# smartwatch-bottom.net
KiCad netlist of a schematic drawn in EAGLE
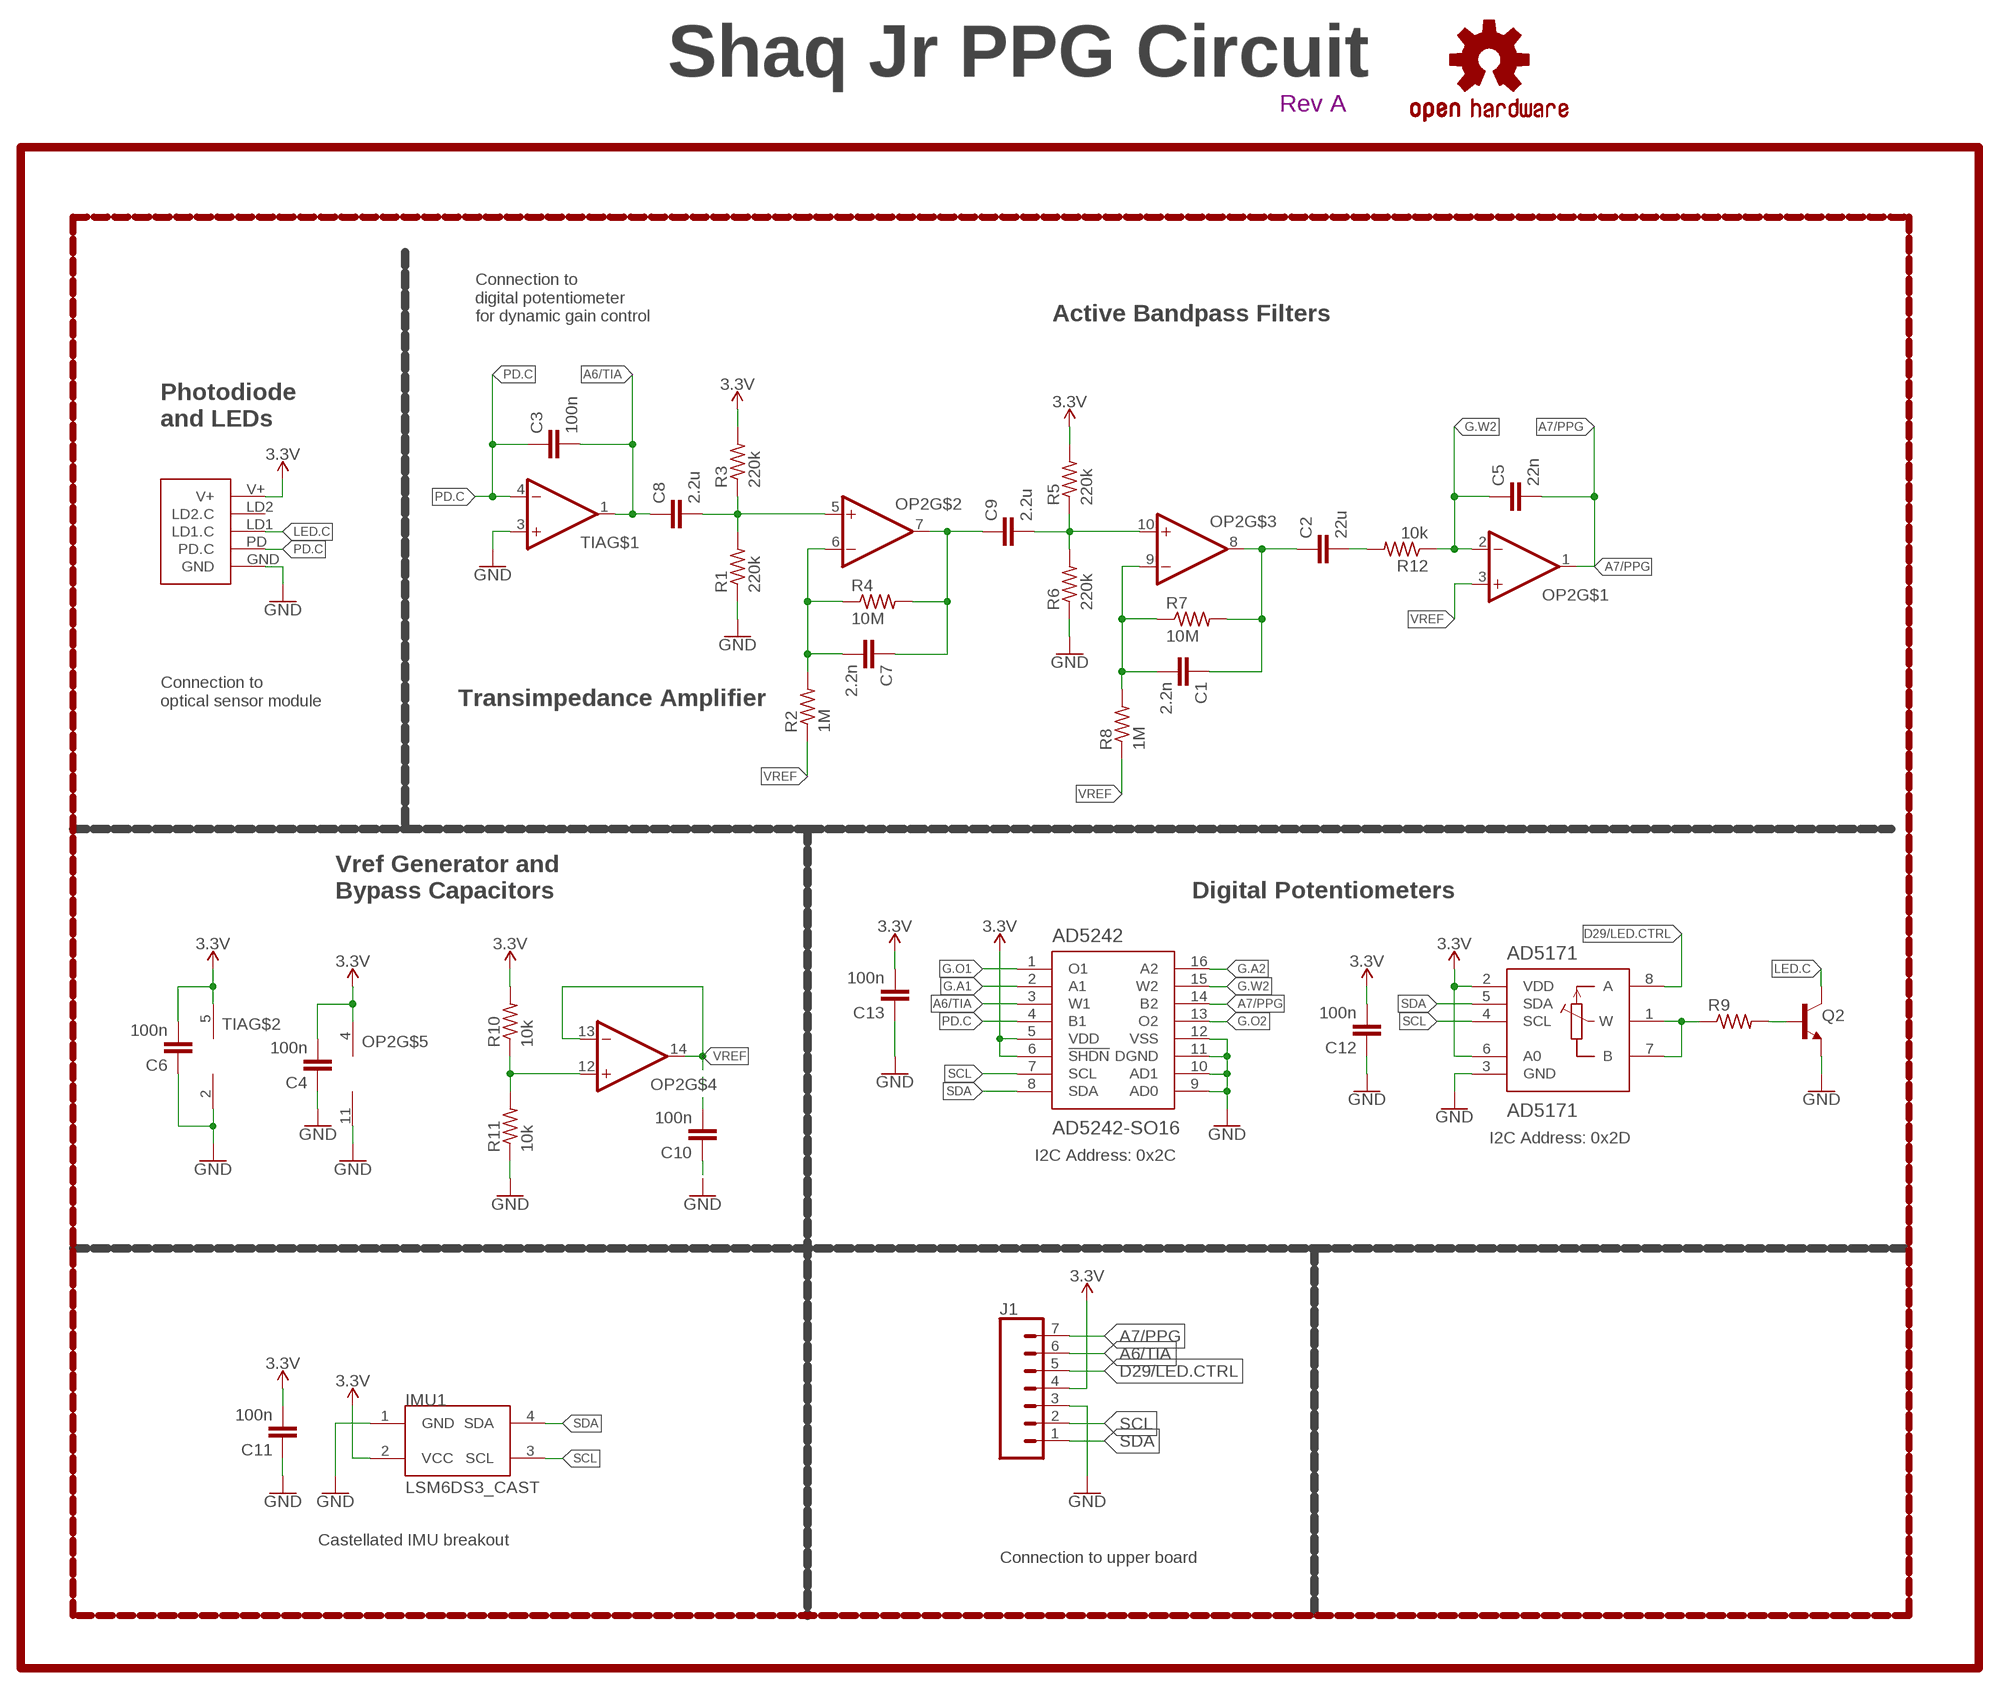
[diagram p0: schematic, sheet 1]

(export (version "E")
  (design (tool "Eeschema 10.0.6"))
  (components
    (comp (ref "AD5171")
      (value "AD5171")
      (footprint "eagle-import:SOT-23-8")
      (libsource (lib "eagle-import") (part "AD5171"))
    )
    (comp (ref "AD5242")
      (value "AD5242-SO16")
      (footprint "eagle-import:SO16")
      (libsource (lib "eagle-import") (part "AD5242-SO16"))
    )
    (comp (ref "C1")
      (value "2.2n")
      (footprint "eagle-import:C0603")
      (libsource (lib "eagle-import") (part "CAPACITOR0603"))
    )
    (comp (ref "C2")
      (value "22u")
      (footprint "eagle-import:C0603")
      (libsource (lib "eagle-import") (part "CAPACITOR0603"))
    )
    (comp (ref "C3")
      (value "100n")
      (footprint "eagle-import:C0603")
      (libsource (lib "eagle-import") (part "CAPACITOR0603"))
    )
    (comp (ref "C4")
      (value "100n")
      (footprint "eagle-import:C0603")
      (libsource (lib "eagle-import") (part "CAPACITOR0603"))
    )
    (comp (ref "C5")
      (value "22n")
      (footprint "eagle-import:C0603")
      (libsource (lib "eagle-import") (part "CAPACITOR0603"))
    )
    (comp (ref "C6")
      (value "100n")
      (footprint "eagle-import:C0603")
      (libsource (lib "eagle-import") (part "CAPACITOR0603"))
    )
    (comp (ref "C7")
      (value "2.2n")
      (footprint "eagle-import:C0603")
      (libsource (lib "eagle-import") (part "CAPACITOR0603"))
    )
    (comp (ref "C8")
      (value "2.2u")
      (footprint "eagle-import:C0603")
      (libsource (lib "eagle-import") (part "CAPACITOR0603"))
    )
    (comp (ref "C9")
      (value "2.2u")
      (footprint "eagle-import:C0603")
      (libsource (lib "eagle-import") (part "CAPACITOR0603"))
    )
    (comp (ref "C10")
      (value "100n")
      (footprint "eagle-import:C0603")
      (libsource (lib "eagle-import") (part "CAPACITOR0603"))
    )
    (comp (ref "C11")
      (value "100n")
      (footprint "eagle-import:C0603")
      (libsource (lib "eagle-import") (part "CAPACITOR0603"))
    )
    (comp (ref "C12")
      (value "100n")
      (footprint "eagle-import:C0603")
      (libsource (lib "eagle-import") (part "CAPACITOR0603"))
    )
    (comp (ref "C13")
      (value "100n")
      (footprint "eagle-import:C0603")
      (libsource (lib "eagle-import") (part "CAPACITOR0603"))
    )
    (comp (ref "IMU1")
      (value "LSM6DS3_CAST")
      (footprint "eagle-import:LSM6DS3_CAST")
      (libsource (lib "eagle-import") (part "LSM6DS3_CAST"))
    )
    (comp (ref "J1")
      (value "CONN_07-1.27MM")
      (footprint "eagle-import:1X07_1.27MM")
      (libsource (lib "eagle-import") (part "CONN_07-1.27MM"))
    )
    (comp (ref "LOGO1")
      (value "REVISION.A")
      (footprint "eagle-import:REV.A")
      (libsource (lib "eagle-import") (part "REVISION.A"))
    )
    (comp (ref "LOGO2")
      (value "OSHW-LOGOS")
      (footprint "eagle-import:OSHW-LOGO-S")
      (libsource (lib "eagle-import") (part "OSHW-LOGOS"))
    )
    (comp (ref "OP2")
      (value "OP-QUAD-SO14")
      (footprint "eagle-import:SO14")
      (libsource (lib "eagle-import") (part "OP-QUAD-SO14"))
    )
    (comp (ref "Q2")
      (value "NPN-GENERIC")
      (footprint "eagle-import:SOT23-3")
      (libsource (lib "eagle-import") (part "NPN-GENERIC"))
    )
    (comp (ref "R1")
      (value "220k")
      (footprint "eagle-import:R0603")
      (libsource (lib "eagle-import") (part "RESISTOR0603"))
    )
    (comp (ref "R2")
      (value "1M")
      (footprint "eagle-import:R0603")
      (libsource (lib "eagle-import") (part "RESISTOR0603"))
    )
    (comp (ref "R3")
      (value "220k")
      (footprint "eagle-import:R0603")
      (libsource (lib "eagle-import") (part "RESISTOR0603"))
    )
    (comp (ref "R4")
      (value "10M")
      (footprint "eagle-import:R0603")
      (libsource (lib "eagle-import") (part "RESISTOR0603"))
    )
    (comp (ref "R5")
      (value "220k")
      (footprint "eagle-import:R0603")
      (libsource (lib "eagle-import") (part "RESISTOR0603"))
    )
    (comp (ref "R6")
      (value "220k")
      (footprint "eagle-import:R0603")
      (libsource (lib "eagle-import") (part "RESISTOR0603"))
    )
    (comp (ref "R7")
      (value "10M")
      (footprint "eagle-import:R0603")
      (libsource (lib "eagle-import") (part "RESISTOR0603"))
    )
    (comp (ref "R8")
      (value "1M")
      (footprint "eagle-import:R0603")
      (libsource (lib "eagle-import") (part "RESISTOR0603"))
    )
    (comp (ref "R9")
      (value "RESISTOR0603")
      (footprint "eagle-import:R0603")
      (libsource (lib "eagle-import") (part "RESISTOR0603"))
    )
    (comp (ref "R10")
      (value "10k")
      (footprint "eagle-import:R0402")
      (libsource (lib "eagle-import") (part "RESISTOR0402"))
    )
    (comp (ref "R11")
      (value "10k")
      (footprint "eagle-import:R0402")
      (libsource (lib "eagle-import") (part "RESISTOR0402"))
    )
    (comp (ref "R12")
      (value "10k")
      (footprint "eagle-import:R0603")
      (libsource (lib "eagle-import") (part "RESISTOR0603"))
    )
    (comp (ref "TIA")
      (value "OP-SINGLEOT")
      (footprint "eagle-import:SOT23-5")
      (libsource (lib "eagle-import") (part "OP-SINGLEOT"))
    )
    (comp (ref "U$1")
      (value "PPG.MODULE.2")
      (footprint "eagle-import:PPG.MODULE.2")
      (libsource (lib "eagle-import") (part "PPG.MODULE.2"))
    )
  )
  (nets
    (net (code "1") (name "3.3V") (class "Default")
      (node (ref "AD5171") (pin "2") (pinfunction "VDD_2") (pintype "bidirectional"))
      (node (ref "AD5171") (pin "6") (pinfunction "A0_6") (pintype "bidirectional"))
      (node (ref "AD5242") (pin "5") (pinfunction "VDD_5") (pintype "bidirectional"))
      (node (ref "AD5242") (pin "6") (pinfunction "~{SHDN}_6") (pintype "bidirectional"))
      (node (ref "C11") (pin "2") (pinfunction "2_2") (pintype "passive"))
      (node (ref "C12") (pin "2") (pinfunction "2_2") (pintype "passive"))
      (node (ref "C13") (pin "2") (pinfunction "2_2") (pintype "passive"))
      (node (ref "C4") (pin "2") (pinfunction "2_2") (pintype "passive"))
      (node (ref "C6") (pin "2") (pinfunction "2_2") (pintype "passive"))
      (node (ref "IMU1") (pin "2") (pinfunction "VCC_2") (pintype "bidirectional"))
      (node (ref "J1") (pin "4") (pinfunction "4_4") (pintype "passive"))
      (node (ref "OP2") (pin "4") (pinfunction "V+_4") (pintype "power_in"))
      (node (ref "R10") (pin "2") (pinfunction "2_2") (pintype "passive"))
      (node (ref "R3") (pin "2") (pinfunction "2_2") (pintype "passive"))
      (node (ref "R5") (pin "2") (pinfunction "2_2") (pintype "passive"))
      (node (ref "TIA") (pin "5") (pinfunction "V+_5") (pintype "power_in"))
      (node (ref "U$1") (pin "V+") (pinfunction "V+_V+") (pintype "bidirectional"))
    )
    (net (code "2") (name "A6{slash}TIA") (class "Default")
      (node (ref "AD5242") (pin "3") (pinfunction "W1_3") (pintype "bidirectional"))
      (node (ref "C3") (pin "2") (pinfunction "2_2") (pintype "passive"))
      (node (ref "C8") (pin "1") (pinfunction "1_1") (pintype "passive"))
      (node (ref "J1") (pin "6") (pinfunction "6_6") (pintype "passive"))
      (node (ref "TIA") (pin "1") (pinfunction "OUT_1") (pintype "output"))
    )
    (net (code "3") (name "A7{slash}PPG") (class "Default")
      (node (ref "AD5242") (pin "14") (pinfunction "B2_14") (pintype "bidirectional"))
      (node (ref "C5") (pin "2") (pinfunction "2_2") (pintype "passive"))
      (node (ref "J1") (pin "7") (pinfunction "7_7") (pintype "passive"))
      (node (ref "OP2") (pin "1") (pinfunction "OUT_1") (pintype "output"))
    )
    (net (code "4") (name "D29{slash}LED.CTRL") (class "Default")
      (node (ref "AD5171") (pin "8") (pinfunction "A_8") (pintype "bidirectional"))
      (node (ref "J1") (pin "5") (pinfunction "5_5") (pintype "passive"))
    )
    (net (code "5") (name "G.A1") (class "Default")
      (node (ref "AD5242") (pin "2") (pinfunction "A1_2") (pintype "bidirectional"))
    )
    (net (code "6") (name "G.A2") (class "Default")
      (node (ref "AD5242") (pin "16") (pinfunction "A2_16") (pintype "bidirectional"))
    )
    (net (code "7") (name "G.O1") (class "Default")
      (node (ref "AD5242") (pin "1") (pinfunction "O1_1") (pintype "bidirectional"))
    )
    (net (code "8") (name "G.O2") (class "Default")
      (node (ref "AD5242") (pin "13") (pinfunction "O2_13") (pintype "bidirectional"))
    )
    (net (code "9") (name "G.W2") (class "Default")
      (node (ref "AD5242") (pin "15") (pinfunction "W2_15") (pintype "bidirectional"))
      (node (ref "C5") (pin "1") (pinfunction "1_1") (pintype "passive"))
      (node (ref "OP2") (pin "2") (pinfunction "-IN_2") (pintype "input"))
      (node (ref "R12") (pin "1") (pinfunction "1_1") (pintype "passive"))
    )
    (net (code "10") (name "GND") (class "Default")
      (node (ref "AD5171") (pin "3") (pinfunction "GND_3") (pintype "bidirectional"))
      (node (ref "AD5242") (pin "10") (pinfunction "AD1_10") (pintype "bidirectional"))
      (node (ref "AD5242") (pin "11") (pinfunction "DGND_11") (pintype "bidirectional"))
      (node (ref "AD5242") (pin "12") (pinfunction "VSS_12") (pintype "bidirectional"))
      (node (ref "AD5242") (pin "9") (pinfunction "AD0_9") (pintype "bidirectional"))
      (node (ref "C10") (pin "1") (pinfunction "1_1") (pintype "passive"))
      (node (ref "C11") (pin "1") (pinfunction "1_1") (pintype "passive"))
      (node (ref "C12") (pin "1") (pinfunction "1_1") (pintype "passive"))
      (node (ref "C13") (pin "1") (pinfunction "1_1") (pintype "passive"))
      (node (ref "C4") (pin "1") (pinfunction "1_1") (pintype "passive"))
      (node (ref "C6") (pin "1") (pinfunction "1_1") (pintype "passive"))
      (node (ref "IMU1") (pin "1") (pinfunction "GND_1") (pintype "bidirectional"))
      (node (ref "J1") (pin "3") (pinfunction "3_3") (pintype "passive"))
      (node (ref "OP2") (pin "11") (pinfunction "V-_11") (pintype "power_in"))
      (node (ref "Q2") (pin "2") (pinfunction "E_2") (pintype "passive"))
      (node (ref "R1") (pin "1") (pinfunction "1_1") (pintype "passive"))
      (node (ref "R11") (pin "1") (pinfunction "1_1") (pintype "passive"))
      (node (ref "R6") (pin "1") (pinfunction "1_1") (pintype "passive"))
      (node (ref "TIA") (pin "2") (pinfunction "V-_2") (pintype "power_in"))
      (node (ref "TIA") (pin "3") (pinfunction "+IN_3") (pintype "input"))
      (node (ref "U$1") (pin "GND") (pinfunction "GND_GND") (pintype "bidirectional"))
    )
    (net (code "11") (name "LED.C") (class "Default")
      (node (ref "Q2") (pin "3") (pinfunction "C_3") (pintype "passive"))
      (node (ref "U$1") (pin "LD1") (pinfunction "LD1.C_LD1") (pintype "bidirectional"))
    )
    (net (code "12") (name "Net-(AD5171-B)") (class "Default")
      (node (ref "AD5171") (pin "1") (pinfunction "W_1") (pintype "bidirectional"))
      (node (ref "AD5171") (pin "7") (pinfunction "B_7") (pintype "bidirectional"))
      (node (ref "R9") (pin "1") (pinfunction "1_1") (pintype "passive"))
    )
    (net (code "13") (name "Net-(C2-Pad2)") (class "Default")
      (node (ref "C2") (pin "2") (pinfunction "2_2") (pintype "passive"))
      (node (ref "R12") (pin "2") (pinfunction "2_2") (pintype "passive"))
    )
    (net (code "14") (name "Net-(OP2B-+IN)") (class "Default")
      (node (ref "C8") (pin "2") (pinfunction "2_2") (pintype "passive"))
      (node (ref "OP2") (pin "5") (pinfunction "+IN_5") (pintype "input"))
      (node (ref "R1") (pin "2") (pinfunction "2_2") (pintype "passive"))
      (node (ref "R3") (pin "1") (pinfunction "1_1") (pintype "passive"))
    )
    (net (code "15") (name "Net-(OP2B--IN)") (class "Default")
      (node (ref "C7") (pin "2") (pinfunction "2_2") (pintype "passive"))
      (node (ref "OP2") (pin "6") (pinfunction "-IN_6") (pintype "input"))
      (node (ref "R2") (pin "2") (pinfunction "2_2") (pintype "passive"))
      (node (ref "R4") (pin "1") (pinfunction "1_1") (pintype "passive"))
    )
    (net (code "16") (name "Net-(OP2B-OUT)") (class "Default")
      (node (ref "C7") (pin "1") (pinfunction "1_1") (pintype "passive"))
      (node (ref "C9") (pin "1") (pinfunction "1_1") (pintype "passive"))
      (node (ref "OP2") (pin "7") (pinfunction "OUT_7") (pintype "output"))
      (node (ref "R4") (pin "2") (pinfunction "2_2") (pintype "passive"))
    )
    (net (code "17") (name "Net-(OP2C-+IN)") (class "Default")
      (node (ref "C9") (pin "2") (pinfunction "2_2") (pintype "passive"))
      (node (ref "OP2") (pin "10") (pinfunction "+IN_10") (pintype "input"))
      (node (ref "R5") (pin "1") (pinfunction "1_1") (pintype "passive"))
      (node (ref "R6") (pin "2") (pinfunction "2_2") (pintype "passive"))
    )
    (net (code "18") (name "Net-(OP2C--IN)") (class "Default")
      (node (ref "C1") (pin "2") (pinfunction "2_2") (pintype "passive"))
      (node (ref "OP2") (pin "9") (pinfunction "-IN_9") (pintype "input"))
      (node (ref "R7") (pin "1") (pinfunction "1_1") (pintype "passive"))
      (node (ref "R8") (pin "2") (pinfunction "2_2") (pintype "passive"))
    )
    (net (code "19") (name "Net-(OP2C-OUT)") (class "Default")
      (node (ref "C1") (pin "1") (pinfunction "1_1") (pintype "passive"))
      (node (ref "C2") (pin "1") (pinfunction "1_1") (pintype "passive"))
      (node (ref "OP2") (pin "8") (pinfunction "OUT_8") (pintype "output"))
      (node (ref "R7") (pin "2") (pinfunction "2_2") (pintype "passive"))
    )
    (net (code "20") (name "Net-(OP2D-+IN)") (class "Default")
      (node (ref "OP2") (pin "12") (pinfunction "+IN_12") (pintype "input"))
      (node (ref "R10") (pin "1") (pinfunction "1_1") (pintype "passive"))
      (node (ref "R11") (pin "2") (pinfunction "2_2") (pintype "passive"))
    )
    (net (code "21") (name "Net-(Q2-B)") (class "Default")
      (node (ref "Q2") (pin "1") (pinfunction "B_1") (pintype "passive"))
      (node (ref "R9") (pin "2") (pinfunction "2_2") (pintype "passive"))
    )
    (net (code "22") (name "PD.C") (class "Default")
      (node (ref "AD5242") (pin "4") (pinfunction "B1_4") (pintype "bidirectional"))
      (node (ref "C3") (pin "1") (pinfunction "1_1") (pintype "passive"))
      (node (ref "TIA") (pin "4") (pinfunction "-IN_4") (pintype "input"))
      (node (ref "U$1") (pin "PD") (pinfunction "PD.C_PD") (pintype "bidirectional"))
    )
    (net (code "23") (name "SCL") (class "Default")
      (node (ref "AD5171") (pin "4") (pinfunction "SCL_4") (pintype "bidirectional"))
      (node (ref "AD5242") (pin "7") (pinfunction "SCL_7") (pintype "bidirectional"))
      (node (ref "IMU1") (pin "3") (pinfunction "SCL_3") (pintype "bidirectional"))
      (node (ref "J1") (pin "2") (pinfunction "2_2") (pintype "passive"))
    )
    (net (code "24") (name "SDA") (class "Default")
      (node (ref "AD5171") (pin "5") (pinfunction "SDA_5") (pintype "bidirectional"))
      (node (ref "AD5242") (pin "8") (pinfunction "SDA_8") (pintype "bidirectional"))
      (node (ref "IMU1") (pin "4") (pinfunction "SDA_4") (pintype "bidirectional"))
      (node (ref "J1") (pin "1") (pinfunction "1_1") (pintype "passive"))
    )
    (net (code "25") (name "VREF") (class "Default")
      (node (ref "C10") (pin "2") (pinfunction "2_2") (pintype "passive"))
      (node (ref "OP2") (pin "13") (pinfunction "-IN_13") (pintype "input"))
      (node (ref "OP2") (pin "14") (pinfunction "OUT_14") (pintype "output"))
      (node (ref "OP2") (pin "3") (pinfunction "+IN_3") (pintype "input"))
      (node (ref "R2") (pin "1") (pinfunction "1_1") (pintype "passive"))
      (node (ref "R8") (pin "1") (pinfunction "1_1") (pintype "passive"))
    )
    (net (code "26") (name "unconnected-(U$1-LD2.C-PadLD2)") (class "Default")
      (node (ref "U$1") (pin "LD2") (pinfunction "LD2.C_LD2") (pintype "bidirectional"))
    )
  )
)
